# TrinketTrigger.net
KiCad netlist of a schematic drawn in EAGLE
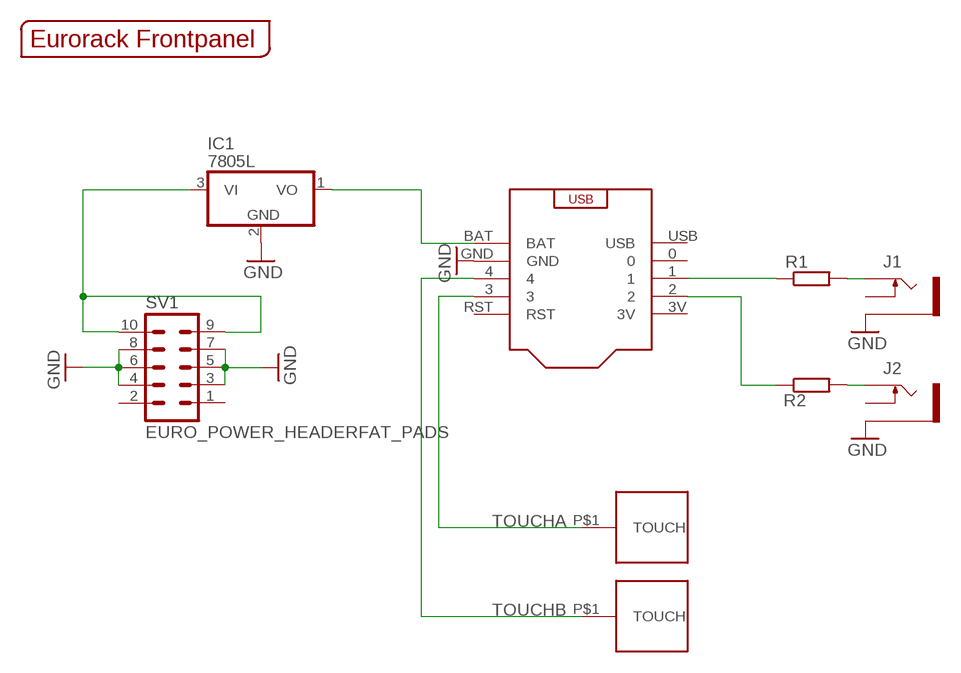
[diagram p0: schematic, sheet 1]

(export (version "E")
  (design (tool "Eeschema 10.0.6"))
  (components
    (comp (ref "IC1")
      (value "7805L")
      (footprint "eagle-import:TO92")
      (libsource (lib "eagle-import") (part "78L05"))
    )
    (comp (ref "J1")
      (value "THONKICONNNEW")
      (footprint "eagle-import:WQP-PJ301M-12_JACK")
      (libsource (lib "eagle-import") (part "THONKICONNNEW"))
    )
    (comp (ref "J2")
      (value "THONKICONNNEW")
      (footprint "eagle-import:WQP-PJ301M-12_JACK")
      (libsource (lib "eagle-import") (part "THONKICONNNEW"))
    )
    (comp (ref "R1")
      (value "R-EU_0204/5")
      (footprint "eagle-import:0204_5")
      (libsource (lib "eagle-import") (part "R-EU_0204/5"))
    )
    (comp (ref "R2")
      (value "R-EU_0204/5")
      (footprint "eagle-import:0204_5")
      (libsource (lib "eagle-import") (part "R-EU_0204/5"))
    )
    (comp (ref "SV1")
      (value "EURO_POWER_HEADERFAT_PADS")
      (footprint "eagle-import:EURO_PWR_HEADER_FAT")
      (libsource (lib "eagle-import") (part "EURO_POWER_HEADERFAT_PADS"))
    )
    (comp (ref "U$1")
      (value "EURORACK_PANEL6HP")
      (footprint "eagle-import:EURORACK6HPPANEL")
      (libsource (lib "eagle-import") (part "EURORACK_PANEL6HP"))
    )
    (comp (ref "U$2")
      (value "TRINKETM0NH")
      (footprint "eagle-import:TRINKETMO_NOHOLES")
      (libsource (lib "eagle-import") (part "TRINKETM0NH"))
    )
    (comp (ref "U$3")
      (value "TOUCHPADA")
      (footprint "eagle-import:TOUCHPADA")
      (libsource (lib "eagle-import") (part "TOUCHPADA"))
    )
    (comp (ref "U$4")
      (value "TOUCHPADA")
      (footprint "eagle-import:TOUCHPADA")
      (libsource (lib "eagle-import") (part "TOUCHPADA"))
    )
  )
  (nets
    (net (code "1") (name "/TOUCHA") (class "Default")
      (node (ref "U$2") (pin "3") (pinfunction "3_3") (pintype "bidirectional"))
      (node (ref "U$3") (pin "P$1") (pinfunction "TOUCH_P$1") (pintype "bidirectional"))
    )
    (net (code "2") (name "/TOUCHB") (class "Default")
      (node (ref "U$2") (pin "4") (pinfunction "4_4") (pintype "bidirectional"))
      (node (ref "U$4") (pin "P$1") (pinfunction "TOUCH_P$1") (pintype "bidirectional"))
    )
    (net (code "3") (name "GND") (class "Default")
      (node (ref "IC1") (pin "2") (pinfunction "GND_2") (pintype "passive"))
      (node (ref "J1") (pin "P$3_SLEEVE") (pinfunction "SLEEVE_P$3_SLEEVE") (pintype "passive"))
      (node (ref "J2") (pin "P$3_SLEEVE") (pinfunction "SLEEVE_P$3_SLEEVE") (pintype "passive"))
      (node (ref "SV1") (pin "3") (pinfunction "3_3") (pintype "passive"))
      (node (ref "SV1") (pin "4") (pinfunction "4_4") (pintype "passive"))
      (node (ref "SV1") (pin "5") (pinfunction "5_5") (pintype "passive"))
      (node (ref "SV1") (pin "6") (pinfunction "6_6") (pintype "passive"))
      (node (ref "SV1") (pin "7") (pinfunction "7_7") (pintype "passive"))
      (node (ref "SV1") (pin "8") (pinfunction "8_8") (pintype "passive"))
      (node (ref "U$2") (pin "GND") (pinfunction "GND_GND") (pintype "bidirectional"))
    )
    (net (code "4") (name "Net-(IC1-VI)") (class "Default")
      (node (ref "IC1") (pin "3") (pinfunction "VI_3") (pintype "input"))
      (node (ref "SV1") (pin "10") (pinfunction "10_10") (pintype "passive"))
      (node (ref "SV1") (pin "9") (pinfunction "9_9") (pintype "passive"))
    )
    (net (code "5") (name "Net-(IC1-VO)") (class "Default")
      (node (ref "IC1") (pin "1") (pinfunction "VO_1") (pintype "passive"))
      (node (ref "U$2") (pin "BAT") (pinfunction "BAT_BAT") (pintype "bidirectional"))
    )
    (net (code "6") (name "Net-(J1-TIP)") (class "Default")
      (node (ref "J1") (pin "P$1_TIP") (pinfunction "TIP_P$1_TIP") (pintype "passive"))
      (node (ref "R1") (pin "2") (pinfunction "2_2") (pintype "passive"))
    )
    (net (code "7") (name "Net-(J2-TIP)") (class "Default")
      (node (ref "J2") (pin "P$1_TIP") (pinfunction "TIP_P$1_TIP") (pintype "passive"))
      (node (ref "R2") (pin "2") (pinfunction "2_2") (pintype "passive"))
    )
    (net (code "8") (name "Net-(R1-Pad1)") (class "Default")
      (node (ref "R1") (pin "1") (pinfunction "1_1") (pintype "passive"))
      (node (ref "U$2") (pin "1") (pinfunction "1_1") (pintype "bidirectional"))
    )
    (net (code "9") (name "Net-(R2-Pad1)") (class "Default")
      (node (ref "R2") (pin "1") (pinfunction "1_1") (pintype "passive"))
      (node (ref "U$2") (pin "2") (pinfunction "2_2") (pintype "bidirectional"))
    )
    (net (code "10") (name "unconnected-(J1-SWITCH-PadP$2_SWITCH)") (class "Default")
      (node (ref "J1") (pin "P$2_SWITCH") (pinfunction "SWITCH_P$2_SWITCH") (pintype "passive"))
    )
    (net (code "11") (name "unconnected-(J2-SWITCH-PadP$2_SWITCH)") (class "Default")
      (node (ref "J2") (pin "P$2_SWITCH") (pinfunction "SWITCH_P$2_SWITCH") (pintype "passive"))
    )
    (net (code "12") (name "unconnected-(SV1-Pad1)") (class "Default")
      (node (ref "SV1") (pin "1") (pinfunction "1_1") (pintype "passive"))
    )
    (net (code "13") (name "unconnected-(SV1-Pad2)") (class "Default")
      (node (ref "SV1") (pin "2") (pinfunction "2_2") (pintype "passive"))
    )
    (net (code "14") (name "unconnected-(U$2-Pad0)") (class "Default")
      (node (ref "U$2") (pin "0") (pinfunction "0_0") (pintype "bidirectional"))
    )
    (net (code "15") (name "unconnected-(U$2-Pad3V)") (class "Default")
      (node (ref "U$2") (pin "3V") (pinfunction "3V_3V") (pintype "bidirectional"))
    )
    (net (code "16") (name "unconnected-(U$2-PadRST)") (class "Default")
      (node (ref "U$2") (pin "RST") (pinfunction "RST_RST") (pintype "bidirectional"))
    )
    (net (code "17") (name "unconnected-(U$2-PadUSB)") (class "Default")
      (node (ref "U$2") (pin "USB") (pinfunction "USB_USB") (pintype "bidirectional"))
    )
  )
)
